# EmbeddedSystem_BackplaneV1.net
KiCad netlist of a schematic drawn in EAGLE
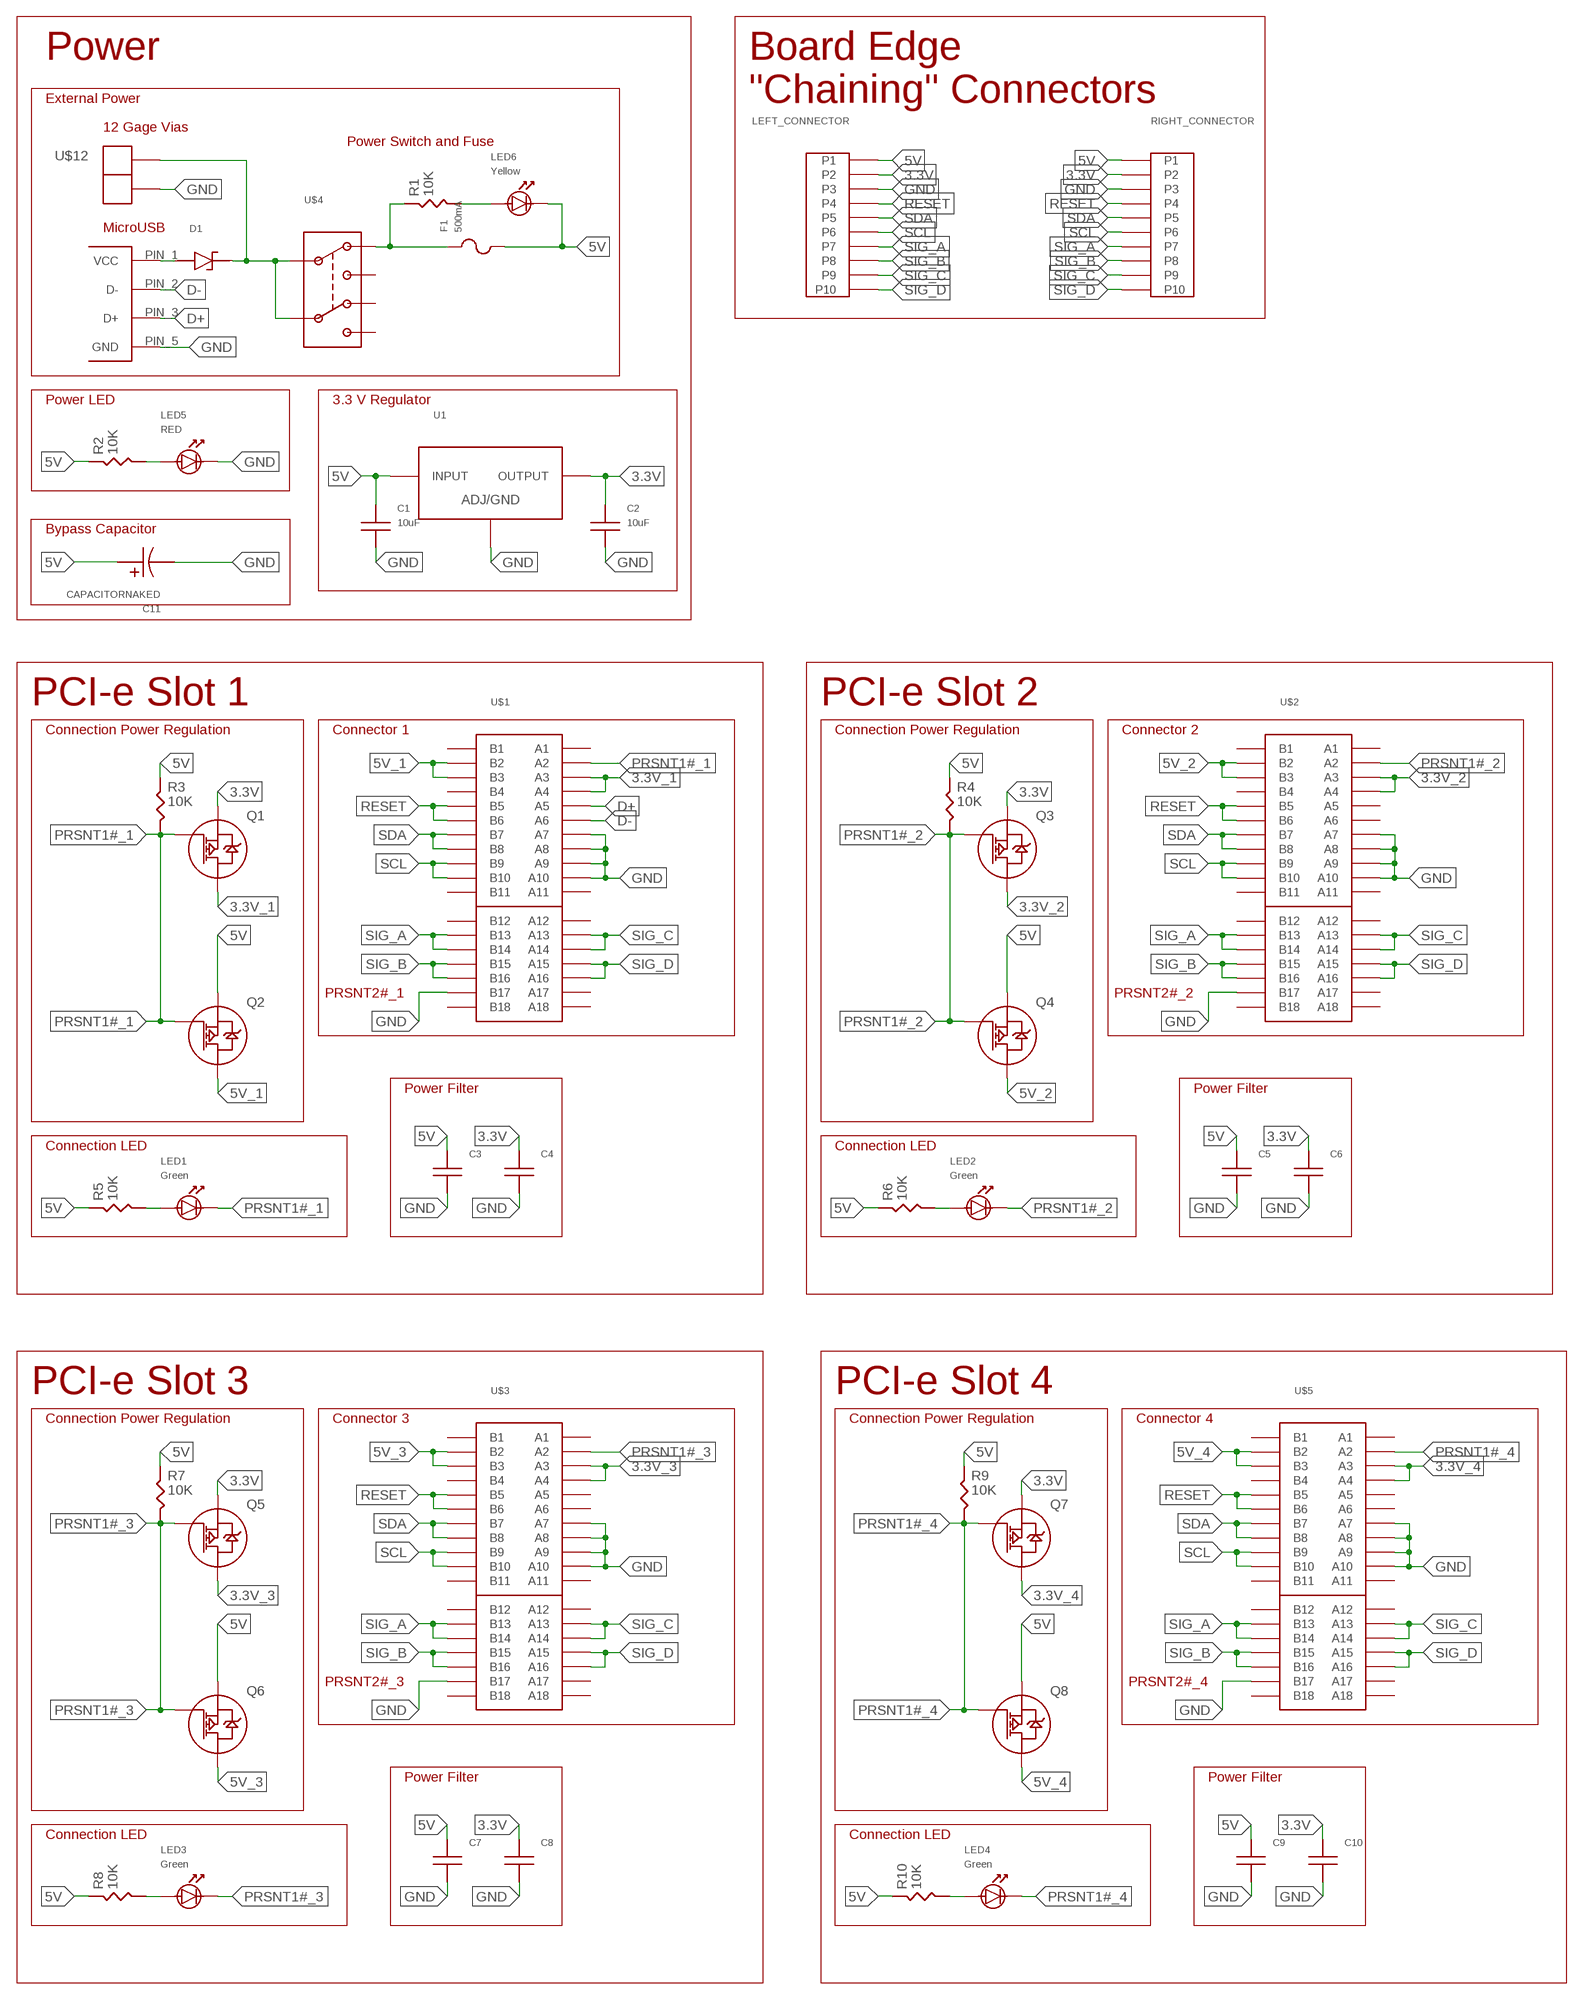
[diagram p0: schematic, sheet 1]

(export (version "E")
  (design (tool "Eeschema 10.0.6"))
  (components
    (comp (ref "C1")
      (value "10uF")
      (footprint "eagle-import:0805_STACKPOLERESISTOR")
      (libsource (lib "eagle-import") (part "CAPACITOR-UNPOLARIZED0805"))
    )
    (comp (ref "C2")
      (value "10uF")
      (footprint "eagle-import:0805_STACKPOLERESISTOR")
      (libsource (lib "eagle-import") (part "CAPACITOR-UNPOLARIZED0805"))
    )
    (comp (ref "C3")
      (value "CAPACITOR-UNPOLARIZED0805")
      (footprint "eagle-import:0805_STACKPOLERESISTOR")
      (libsource (lib "eagle-import") (part "CAPACITOR-UNPOLARIZED0805"))
    )
    (comp (ref "C4")
      (value "CAPACITOR-UNPOLARIZED0805")
      (footprint "eagle-import:0805_STACKPOLERESISTOR")
      (libsource (lib "eagle-import") (part "CAPACITOR-UNPOLARIZED0805"))
    )
    (comp (ref "C5")
      (value "CAPACITOR-UNPOLARIZED0805")
      (footprint "eagle-import:0805_STACKPOLERESISTOR")
      (libsource (lib "eagle-import") (part "CAPACITOR-UNPOLARIZED0805"))
    )
    (comp (ref "C6")
      (value "CAPACITOR-UNPOLARIZED0805")
      (footprint "eagle-import:0805_STACKPOLERESISTOR")
      (libsource (lib "eagle-import") (part "CAPACITOR-UNPOLARIZED0805"))
    )
    (comp (ref "C7")
      (value "CAPACITOR-UNPOLARIZED0805")
      (footprint "eagle-import:0805_STACKPOLERESISTOR")
      (libsource (lib "eagle-import") (part "CAPACITOR-UNPOLARIZED0805"))
    )
    (comp (ref "C8")
      (value "CAPACITOR-UNPOLARIZED0805")
      (footprint "eagle-import:0805_STACKPOLERESISTOR")
      (libsource (lib "eagle-import") (part "CAPACITOR-UNPOLARIZED0805"))
    )
    (comp (ref "C9")
      (value "CAPACITOR-UNPOLARIZED0805")
      (footprint "eagle-import:0805_STACKPOLERESISTOR")
      (libsource (lib "eagle-import") (part "CAPACITOR-UNPOLARIZED0805"))
    )
    (comp (ref "C10")
      (value "CAPACITOR-UNPOLARIZED0805")
      (footprint "eagle-import:0805_STACKPOLERESISTOR")
      (libsource (lib "eagle-import") (part "CAPACITOR-UNPOLARIZED0805"))
    )
    (comp (ref "C11")
      (value "CAPACITORNAKED")
      (footprint "eagle-import:ESK_H4_CAPACITOR_NAKED")
      (libsource (lib "eagle-import") (part "CAPACITORNAKED"))
    )
    (comp (ref "D1")
      (value "DIODE_SCHOTTKYSOD-123")
      (footprint "eagle-import:SOD-123")
      (libsource (lib "eagle-import") (part "DIODE_SCHOTTKYSOD-123"))
    )
    (comp (ref "F1")
      (value "500mA")
      (footprint "eagle-import:TYPE_C1Q_FUSE")
      (libsource (lib "eagle-import") (part "FUSEC1Q_SMD"))
    )
    (comp (ref "LED1")
      (value "Green")
      (footprint "eagle-import:0805_LED")
      (libsource (lib "eagle-import") (part "LED"))
    )
    (comp (ref "LED2")
      (value "Green")
      (footprint "eagle-import:0805_LED")
      (libsource (lib "eagle-import") (part "LED"))
    )
    (comp (ref "LED3")
      (value "Green")
      (footprint "eagle-import:0805_LED")
      (libsource (lib "eagle-import") (part "LED"))
    )
    (comp (ref "LED4")
      (value "Green")
      (footprint "eagle-import:0805_LED")
      (libsource (lib "eagle-import") (part "LED"))
    )
    (comp (ref "LED5")
      (value "RED")
      (footprint "eagle-import:0805_LED")
      (libsource (lib "eagle-import") (part "LED"))
    )
    (comp (ref "LED6")
      (value "Yellow")
      (footprint "eagle-import:0805_LED")
      (libsource (lib "eagle-import") (part "LED"))
    )
    (comp (ref "LEFT_CONNECTOR")
      (value "10PIN-HEADER")
      (footprint "eagle-import:10PIN_HEADER")
      (libsource (lib "eagle-import") (part "10PIN-HEADER"))
    )
    (comp (ref "Q1")
      (value "PMOSSOT-23")
      (footprint "eagle-import:SOT-23")
      (libsource (lib "eagle-import") (part "PMOSSOT-23"))
    )
    (comp (ref "Q2")
      (value "PMOSSOT-23")
      (footprint "eagle-import:SOT-23")
      (libsource (lib "eagle-import") (part "PMOSSOT-23"))
    )
    (comp (ref "Q3")
      (value "PMOSSOT-23")
      (footprint "eagle-import:SOT-23")
      (libsource (lib "eagle-import") (part "PMOSSOT-23"))
    )
    (comp (ref "Q4")
      (value "PMOSSOT-23")
      (footprint "eagle-import:SOT-23")
      (libsource (lib "eagle-import") (part "PMOSSOT-23"))
    )
    (comp (ref "Q5")
      (value "PMOSSOT-23")
      (footprint "eagle-import:SOT-23")
      (libsource (lib "eagle-import") (part "PMOSSOT-23"))
    )
    (comp (ref "Q6")
      (value "PMOSSOT-23")
      (footprint "eagle-import:SOT-23")
      (libsource (lib "eagle-import") (part "PMOSSOT-23"))
    )
    (comp (ref "Q7")
      (value "PMOSSOT-23")
      (footprint "eagle-import:SOT-23")
      (libsource (lib "eagle-import") (part "PMOSSOT-23"))
    )
    (comp (ref "Q8")
      (value "PMOSSOT-23")
      (footprint "eagle-import:SOT-23")
      (libsource (lib "eagle-import") (part "PMOSSOT-23"))
    )
    (comp (ref "R1")
      (value "10K")
      (footprint "eagle-import:0805_STACKPOLERESISTOR")
      (libsource (lib "eagle-import") (part "RESISTOR"))
    )
    (comp (ref "R2")
      (value "10K")
      (footprint "eagle-import:0805_STACKPOLERESISTOR")
      (libsource (lib "eagle-import") (part "RESISTOR"))
    )
    (comp (ref "R3")
      (value "10K")
      (footprint "eagle-import:0805_STACKPOLERESISTOR")
      (libsource (lib "eagle-import") (part "RESISTOR"))
    )
    (comp (ref "R4")
      (value "10K")
      (footprint "eagle-import:0805_STACKPOLERESISTOR")
      (libsource (lib "eagle-import") (part "RESISTOR"))
    )
    (comp (ref "R5")
      (value "10K")
      (footprint "eagle-import:0805_STACKPOLERESISTOR")
      (libsource (lib "eagle-import") (part "RESISTOR"))
    )
    (comp (ref "R6")
      (value "10K")
      (footprint "eagle-import:0805_STACKPOLERESISTOR")
      (libsource (lib "eagle-import") (part "RESISTOR"))
    )
    (comp (ref "R7")
      (value "10K")
      (footprint "eagle-import:0805_STACKPOLERESISTOR")
      (libsource (lib "eagle-import") (part "RESISTOR"))
    )
    (comp (ref "R8")
      (value "10K")
      (footprint "eagle-import:0805_STACKPOLERESISTOR")
      (libsource (lib "eagle-import") (part "RESISTOR"))
    )
    (comp (ref "R9")
      (value "10K")
      (footprint "eagle-import:0805_STACKPOLERESISTOR")
      (libsource (lib "eagle-import") (part "RESISTOR"))
    )
    (comp (ref "R10")
      (value "10K")
      (footprint "eagle-import:0805_STACKPOLERESISTOR")
      (libsource (lib "eagle-import") (part "RESISTOR"))
    )
    (comp (ref "RIGHT_CONNECTOR")
      (value "10PIN-HEADER")
      (footprint "eagle-import:10PIN_HEADER")
      (libsource (lib "eagle-import") (part "10PIN-HEADER"))
    )
    (comp (ref "U$1")
      (value "PCI-E_X1")
      (footprint "eagle-import:PCIE_X1")
      (libsource (lib "eagle-import") (part "PCI-E_X1"))
    )
    (comp (ref "U$2")
      (value "PCI-E_X1")
      (footprint "eagle-import:PCIE_X1")
      (libsource (lib "eagle-import") (part "PCI-E_X1"))
    )
    (comp (ref "U$3")
      (value "PCI-E_X1")
      (footprint "eagle-import:PCIE_X1")
      (libsource (lib "eagle-import") (part "PCI-E_X1"))
    )
    (comp (ref "U$4")
      (value "SWITCH_DPDT")
      (footprint "eagle-import:SWITCH_GF-126")
      (libsource (lib "eagle-import") (part "SWITCH_DPDT"))
    )
    (comp (ref "U$5")
      (value "PCI-E_X1")
      (footprint "eagle-import:PCIE_X1")
      (libsource (lib "eagle-import") (part "PCI-E_X1"))
    )
    (comp (ref "U$10")
      (value "USBMICROB")
      (footprint "eagle-import:USBMICROB-PAC")
      (libsource (lib "eagle-import") (part "USBMICROB"))
    )
    (comp (ref "U$12")
      (value "2PIN-HEADER16GAGE")
      (footprint "eagle-import:2PIN_16GAGE")
      (libsource (lib "eagle-import") (part "2PIN-HEADER16GAGE"))
    )
    (comp (ref "U1")
      (value "VOLTAGE_REGULATOR")
      (footprint "eagle-import:SOT223")
      (libsource (lib "eagle-import") (part "VOLTAGE_REGULATOR"))
    )
  )
  (nets
    (net (code "1") (name "3.3V") (class "Default")
      (node (ref "C10") (pin "P$1") (pinfunction "P$1_P$1") (pintype "bidirectional"))
      (node (ref "C2") (pin "P$1") (pinfunction "P$1_P$1") (pintype "bidirectional"))
      (node (ref "C4") (pin "P$1") (pinfunction "P$1_P$1") (pintype "bidirectional"))
      (node (ref "C6") (pin "P$1") (pinfunction "P$1_P$1") (pintype "bidirectional"))
      (node (ref "C8") (pin "P$1") (pinfunction "P$1_P$1") (pintype "bidirectional"))
      (node (ref "LEFT_CONNECTOR") (pin "P2") (pinfunction "P2_P2") (pintype "bidirectional"))
      (node (ref "Q1") (pin "S") (pinfunction "S_S") (pintype "bidirectional"))
      (node (ref "Q3") (pin "S") (pinfunction "S_S") (pintype "bidirectional"))
      (node (ref "Q5") (pin "S") (pinfunction "S_S") (pintype "bidirectional"))
      (node (ref "Q7") (pin "S") (pinfunction "S_S") (pintype "bidirectional"))
      (node (ref "RIGHT_CONNECTOR") (pin "P2") (pinfunction "P2_P2") (pintype "bidirectional"))
      (node (ref "U1") (pin "P2") (pinfunction "OUTPUT_P2") (pintype "bidirectional"))
      (node (ref "U1") (pin "TOP") (pinfunction "OUTPUT_TOP") (pintype "bidirectional"))
    )
    (net (code "2") (name "3.3V_1") (class "Default")
      (node (ref "Q1") (pin "D") (pinfunction "D_D") (pintype "bidirectional"))
      (node (ref "U$1") (pin "A3") (pinfunction "A3_A3") (pintype "bidirectional"))
      (node (ref "U$1") (pin "A4") (pinfunction "A4_A4") (pintype "bidirectional"))
    )
    (net (code "3") (name "3.3V_2") (class "Default")
      (node (ref "Q3") (pin "D") (pinfunction "D_D") (pintype "bidirectional"))
      (node (ref "U$2") (pin "A3") (pinfunction "A3_A3") (pintype "bidirectional"))
      (node (ref "U$2") (pin "A4") (pinfunction "A4_A4") (pintype "bidirectional"))
    )
    (net (code "4") (name "3.3V_3") (class "Default")
      (node (ref "Q5") (pin "D") (pinfunction "D_D") (pintype "bidirectional"))
      (node (ref "U$3") (pin "A3") (pinfunction "A3_A3") (pintype "bidirectional"))
      (node (ref "U$3") (pin "A4") (pinfunction "A4_A4") (pintype "bidirectional"))
    )
    (net (code "5") (name "3.3V_4") (class "Default")
      (node (ref "Q7") (pin "D") (pinfunction "D_D") (pintype "bidirectional"))
      (node (ref "U$5") (pin "A3") (pinfunction "A3_A3") (pintype "bidirectional"))
      (node (ref "U$5") (pin "A4") (pinfunction "A4_A4") (pintype "bidirectional"))
    )
    (net (code "6") (name "5V") (class "Default")
      (node (ref "C1") (pin "P$1") (pinfunction "P$1_P$1") (pintype "bidirectional"))
      (node (ref "C11") (pin "POSITIVE_PAD") (pinfunction "POSITIVE_LEAD_POSITIVE_PAD") (pintype "bidirectional"))
      (node (ref "C3") (pin "P$1") (pinfunction "P$1_P$1") (pintype "bidirectional"))
      (node (ref "C5") (pin "P$1") (pinfunction "P$1_P$1") (pintype "bidirectional"))
      (node (ref "C7") (pin "P$1") (pinfunction "P$1_P$1") (pintype "bidirectional"))
      (node (ref "C9") (pin "P$1") (pinfunction "P$1_P$1") (pintype "bidirectional"))
      (node (ref "F1") (pin "P$2") (pinfunction "P$2_P$2") (pintype "bidirectional"))
      (node (ref "LED6") (pin "CATHODE") (pinfunction "CATHODE_CATHODE") (pintype "bidirectional"))
      (node (ref "LEFT_CONNECTOR") (pin "P1") (pinfunction "P1_P1") (pintype "bidirectional"))
      (node (ref "Q2") (pin "S") (pinfunction "S_S") (pintype "bidirectional"))
      (node (ref "Q4") (pin "S") (pinfunction "S_S") (pintype "bidirectional"))
      (node (ref "Q6") (pin "S") (pinfunction "S_S") (pintype "bidirectional"))
      (node (ref "Q8") (pin "S") (pinfunction "S_S") (pintype "bidirectional"))
      (node (ref "R10") (pin "P$1") (pinfunction "P$1_P$1") (pintype "bidirectional"))
      (node (ref "R2") (pin "P$1") (pinfunction "P$1_P$1") (pintype "bidirectional"))
      (node (ref "R3") (pin "P$1") (pinfunction "P$1_P$1") (pintype "bidirectional"))
      (node (ref "R4") (pin "P$1") (pinfunction "P$1_P$1") (pintype "bidirectional"))
      (node (ref "R5") (pin "P$1") (pinfunction "P$1_P$1") (pintype "bidirectional"))
      (node (ref "R6") (pin "P$1") (pinfunction "P$1_P$1") (pintype "bidirectional"))
      (node (ref "R7") (pin "P$1") (pinfunction "P$1_P$1") (pintype "bidirectional"))
      (node (ref "R8") (pin "P$1") (pinfunction "P$1_P$1") (pintype "bidirectional"))
      (node (ref "R9") (pin "P$1") (pinfunction "P$1_P$1") (pintype "bidirectional"))
      (node (ref "RIGHT_CONNECTOR") (pin "P1") (pinfunction "P1_P1") (pintype "bidirectional"))
      (node (ref "U1") (pin "P3") (pinfunction "INPUT_P3") (pintype "bidirectional"))
    )
    (net (code "7") (name "5V_1") (class "Default")
      (node (ref "Q2") (pin "D") (pinfunction "D_D") (pintype "bidirectional"))
      (node (ref "U$1") (pin "B2") (pinfunction "B2_B2") (pintype "bidirectional"))
      (node (ref "U$1") (pin "B3") (pinfunction "B3_B3") (pintype "bidirectional"))
    )
    (net (code "8") (name "5V_2") (class "Default")
      (node (ref "Q4") (pin "D") (pinfunction "D_D") (pintype "bidirectional"))
      (node (ref "U$2") (pin "B2") (pinfunction "B2_B2") (pintype "bidirectional"))
      (node (ref "U$2") (pin "B3") (pinfunction "B3_B3") (pintype "bidirectional"))
    )
    (net (code "9") (name "5V_3") (class "Default")
      (node (ref "Q6") (pin "D") (pinfunction "D_D") (pintype "bidirectional"))
      (node (ref "U$3") (pin "B2") (pinfunction "B2_B2") (pintype "bidirectional"))
      (node (ref "U$3") (pin "B3") (pinfunction "B3_B3") (pintype "bidirectional"))
    )
    (net (code "10") (name "5V_4") (class "Default")
      (node (ref "Q8") (pin "D") (pinfunction "D_D") (pintype "bidirectional"))
      (node (ref "U$5") (pin "B2") (pinfunction "B2_B2") (pintype "bidirectional"))
      (node (ref "U$5") (pin "B3") (pinfunction "B3_B3") (pintype "bidirectional"))
    )
    (net (code "11") (name "D+") (class "Default")
      (node (ref "U$1") (pin "A5") (pinfunction "A5_A5") (pintype "bidirectional"))
      (node (ref "U$10") (pin "PIN_3") (pinfunction "D+_PIN_3") (pintype "bidirectional"))
    )
    (net (code "12") (name "D-") (class "Default")
      (node (ref "U$1") (pin "A6") (pinfunction "A6_A6") (pintype "bidirectional"))
      (node (ref "U$10") (pin "PIN_2") (pinfunction "D-_PIN_2") (pintype "bidirectional"))
    )
    (net (code "13") (name "GND") (class "Default")
      (node (ref "C1") (pin "P$2") (pinfunction "P$2_P$2") (pintype "bidirectional"))
      (node (ref "C10") (pin "P$2") (pinfunction "P$2_P$2") (pintype "bidirectional"))
      (node (ref "C11") (pin "NEGATIVE_PAD") (pinfunction "NEGATIVE_LEAD_NEGATIVE_PAD") (pintype "bidirectional"))
      (node (ref "C2") (pin "P$2") (pinfunction "P$2_P$2") (pintype "bidirectional"))
      (node (ref "C3") (pin "P$2") (pinfunction "P$2_P$2") (pintype "bidirectional"))
      (node (ref "C4") (pin "P$2") (pinfunction "P$2_P$2") (pintype "bidirectional"))
      (node (ref "C5") (pin "P$2") (pinfunction "P$2_P$2") (pintype "bidirectional"))
      (node (ref "C6") (pin "P$2") (pinfunction "P$2_P$2") (pintype "bidirectional"))
      (node (ref "C7") (pin "P$2") (pinfunction "P$2_P$2") (pintype "bidirectional"))
      (node (ref "C8") (pin "P$2") (pinfunction "P$2_P$2") (pintype "bidirectional"))
      (node (ref "C9") (pin "P$2") (pinfunction "P$2_P$2") (pintype "bidirectional"))
      (node (ref "LED5") (pin "CATHODE") (pinfunction "CATHODE_CATHODE") (pintype "bidirectional"))
      (node (ref "LEFT_CONNECTOR") (pin "P3") (pinfunction "P3_P3") (pintype "bidirectional"))
      (node (ref "RIGHT_CONNECTOR") (pin "P3") (pinfunction "P3_P3") (pintype "bidirectional"))
      (node (ref "U$1") (pin "A10") (pinfunction "A10_A10") (pintype "bidirectional"))
      (node (ref "U$1") (pin "A7") (pinfunction "A7_A7") (pintype "bidirectional"))
      (node (ref "U$1") (pin "A8") (pinfunction "A8_A8") (pintype "bidirectional"))
      (node (ref "U$1") (pin "A9") (pinfunction "A9_A9") (pintype "bidirectional"))
      (node (ref "U$1") (pin "B17") (pinfunction "B17_B17") (pintype "bidirectional"))
      (node (ref "U$10") (pin "PIN_5") (pinfunction "GND_PIN_5") (pintype "bidirectional"))
      (node (ref "U$12") (pin "P2") (pinfunction "P$2_P2") (pintype "bidirectional"))
      (node (ref "U$2") (pin "A10") (pinfunction "A10_A10") (pintype "bidirectional"))
      (node (ref "U$2") (pin "A7") (pinfunction "A7_A7") (pintype "bidirectional"))
      (node (ref "U$2") (pin "A8") (pinfunction "A8_A8") (pintype "bidirectional"))
      (node (ref "U$2") (pin "A9") (pinfunction "A9_A9") (pintype "bidirectional"))
      (node (ref "U$2") (pin "B17") (pinfunction "B17_B17") (pintype "bidirectional"))
      (node (ref "U$3") (pin "A10") (pinfunction "A10_A10") (pintype "bidirectional"))
      (node (ref "U$3") (pin "A7") (pinfunction "A7_A7") (pintype "bidirectional"))
      (node (ref "U$3") (pin "A8") (pinfunction "A8_A8") (pintype "bidirectional"))
      (node (ref "U$3") (pin "A9") (pinfunction "A9_A9") (pintype "bidirectional"))
      (node (ref "U$3") (pin "B17") (pinfunction "B17_B17") (pintype "bidirectional"))
      (node (ref "U$5") (pin "A10") (pinfunction "A10_A10") (pintype "bidirectional"))
      (node (ref "U$5") (pin "A7") (pinfunction "A7_A7") (pintype "bidirectional"))
      (node (ref "U$5") (pin "A8") (pinfunction "A8_A8") (pintype "bidirectional"))
      (node (ref "U$5") (pin "A9") (pinfunction "A9_A9") (pintype "bidirectional"))
      (node (ref "U$5") (pin "B17") (pinfunction "B17_B17") (pintype "bidirectional"))
      (node (ref "U1") (pin "P1") (pinfunction "ADJ/GND_P1") (pintype "bidirectional"))
    )
    (net (code "14") (name "Net-(F1-PadP$1)") (class "Default")
      (node (ref "F1") (pin "P$1") (pinfunction "P$1_P$1") (pintype "bidirectional"))
      (node (ref "R1") (pin "P$1") (pinfunction "P$1_P$1") (pintype "bidirectional"))
      (node (ref "U$4") (pin "P1_1") (pinfunction "P1_1_P1_1") (pintype "bidirectional"))
    )
    (net (code "15") (name "Net-(LED1-PadANODE)") (class "Default")
      (node (ref "LED1") (pin "ANODE") (pinfunction "ANODE_ANODE") (pintype "bidirectional"))
      (node (ref "R5") (pin "P$2") (pinfunction "P$2_P$2") (pintype "bidirectional"))
    )
    (net (code "16") (name "Net-(LED2-PadANODE)") (class "Default")
      (node (ref "LED2") (pin "ANODE") (pinfunction "ANODE_ANODE") (pintype "bidirectional"))
      (node (ref "R6") (pin "P$2") (pinfunction "P$2_P$2") (pintype "bidirectional"))
    )
    (net (code "17") (name "Net-(LED3-PadANODE)") (class "Default")
      (node (ref "LED3") (pin "ANODE") (pinfunction "ANODE_ANODE") (pintype "bidirectional"))
      (node (ref "R8") (pin "P$2") (pinfunction "P$2_P$2") (pintype "bidirectional"))
    )
    (net (code "18") (name "Net-(LED4-PadANODE)") (class "Default")
      (node (ref "LED4") (pin "ANODE") (pinfunction "ANODE_ANODE") (pintype "bidirectional"))
      (node (ref "R10") (pin "P$2") (pinfunction "P$2_P$2") (pintype "bidirectional"))
    )
    (net (code "19") (name "Net-(LED5-PadANODE)") (class "Default")
      (node (ref "LED5") (pin "ANODE") (pinfunction "ANODE_ANODE") (pintype "bidirectional"))
      (node (ref "R2") (pin "P$2") (pinfunction "P$2_P$2") (pintype "bidirectional"))
    )
    (net (code "20") (name "Net-(LED6-PadANODE)") (class "Default")
      (node (ref "LED6") (pin "ANODE") (pinfunction "ANODE_ANODE") (pintype "bidirectional"))
      (node (ref "R1") (pin "P$2") (pinfunction "P$2_P$2") (pintype "bidirectional"))
    )
    (net (code "21") (name "Net-(U$10-VCC)") (class "Default")
      (node (ref "D1") (pin "ANODE") (pinfunction "ANODE_ANODE") (pintype "bidirectional"))
      (node (ref "U$10") (pin "PIN_1") (pinfunction "VCC_PIN_1") (pintype "bidirectional"))
    )
    (net (code "22") (name "Net-(U$12-P$1)") (class "Default")
      (node (ref "D1") (pin "CATHODE") (pinfunction "CATHODE_CATHODE") (pintype "bidirectional"))
      (node (ref "U$12") (pin "P1") (pinfunction "P$1_P1") (pintype "bidirectional"))
      (node (ref "U$4") (pin "P1_C") (pinfunction "P1_C_P1_C") (pintype "bidirectional"))
      (node (ref "U$4") (pin "P2_C") (pinfunction "P2_C_P2_C") (pintype "bidirectional"))
    )
    (net (code "23") (name "PRSNT1#_1") (class "Default")
      (node (ref "LED1") (pin "CATHODE") (pinfunction "CATHODE_CATHODE") (pintype "bidirectional"))
      (node (ref "Q1") (pin "G") (pinfunction "G(1)_G") (pintype "bidirectional"))
      (node (ref "Q2") (pin "G") (pinfunction "G(1)_G") (pintype "bidirectional"))
      (node (ref "R3") (pin "P$2") (pinfunction "P$2_P$2") (pintype "bidirectional"))
      (node (ref "U$1") (pin "A2") (pinfunction "A2_A2") (pintype "bidirectional"))
    )
    (net (code "24") (name "PRSNT1#_2") (class "Default")
      (node (ref "LED2") (pin "CATHODE") (pinfunction "CATHODE_CATHODE") (pintype "bidirectional"))
      (node (ref "Q3") (pin "G") (pinfunction "G(1)_G") (pintype "bidirectional"))
      (node (ref "Q4") (pin "G") (pinfunction "G(1)_G") (pintype "bidirectional"))
      (node (ref "R4") (pin "P$2") (pinfunction "P$2_P$2") (pintype "bidirectional"))
      (node (ref "U$2") (pin "A2") (pinfunction "A2_A2") (pintype "bidirectional"))
    )
    (net (code "25") (name "PRSNT1#_3") (class "Default")
      (node (ref "LED3") (pin "CATHODE") (pinfunction "CATHODE_CATHODE") (pintype "bidirectional"))
      (node (ref "Q5") (pin "G") (pinfunction "G(1)_G") (pintype "bidirectional"))
      (node (ref "Q6") (pin "G") (pinfunction "G(1)_G") (pintype "bidirectional"))
      (node (ref "R7") (pin "P$2") (pinfunction "P$2_P$2") (pintype "bidirectional"))
      (node (ref "U$3") (pin "A2") (pinfunction "A2_A2") (pintype "bidirectional"))
    )
    (net (code "26") (name "PRSNT1#_4") (class "Default")
      (node (ref "LED4") (pin "CATHODE") (pinfunction "CATHODE_CATHODE") (pintype "bidirectional"))
      (node (ref "Q7") (pin "G") (pinfunction "G(1)_G") (pintype "bidirectional"))
      (node (ref "Q8") (pin "G") (pinfunction "G(1)_G") (pintype "bidirectional"))
      (node (ref "R9") (pin "P$2") (pinfunction "P$2_P$2") (pintype "bidirectional"))
      (node (ref "U$5") (pin "A2") (pinfunction "A2_A2") (pintype "bidirectional"))
    )
    (net (code "27") (name "RESET") (class "Default")
      (node (ref "LEFT_CONNECTOR") (pin "P4") (pinfunction "P4_P4") (pintype "bidirectional"))
      (node (ref "RIGHT_CONNECTOR") (pin "P4") (pinfunction "P4_P4") (pintype "bidirectional"))
      (node (ref "U$1") (pin "B5") (pinfunction "B5_B5") (pintype "bidirectional"))
      (node (ref "U$1") (pin "B6") (pinfunction "B6_B6") (pintype "bidirectional"))
      (node (ref "U$2") (pin "B5") (pinfunction "B5_B5") (pintype "bidirectional"))
      (node (ref "U$2") (pin "B6") (pinfunction "B6_B6") (pintype "bidirectional"))
      (node (ref "U$3") (pin "B5") (pinfunction "B5_B5") (pintype "bidirectional"))
      (node (ref "U$3") (pin "B6") (pinfunction "B6_B6") (pintype "bidirectional"))
      (node (ref "U$5") (pin "B5") (pinfunction "B5_B5") (pintype "bidirectional"))
      (node (ref "U$5") (pin "B6") (pinfunction "B6_B6") (pintype "bidirectional"))
    )
    (net (code "28") (name "SCL") (class "Default")
      (node (ref "LEFT_CONNECTOR") (pin "P6") (pinfunction "P6_P6") (pintype "bidirectional"))
      (node (ref "RIGHT_CONNECTOR") (pin "P6") (pinfunction "P6_P6") (pintype "bidirectional"))
      (node (ref "U$1") (pin "B10") (pinfunction "B10_B10") (pintype "bidirectional"))
      (node (ref "U$1") (pin "B9") (pinfunction "B9_B9") (pintype "bidirectional"))
      (node (ref "U$2") (pin "B10") (pinfunction "B10_B10") (pintype "bidirectional"))
      (node (ref "U$2") (pin "B9") (pinfunction "B9_B9") (pintype "bidirectional"))
      (node (ref "U$3") (pin "B10") (pinfunction "B10_B10") (pintype "bidirectional"))
      (node (ref "U$3") (pin "B9") (pinfunction "B9_B9") (pintype "bidirectional"))
      (node (ref "U$5") (pin "B10") (pinfunction "B10_B10") (pintype "bidirectional"))
      (node (ref "U$5") (pin "B9") (pinfunction "B9_B9") (pintype "bidirectional"))
    )
    (net (code "29") (name "SDA") (class "Default")
      (node (ref "LEFT_CONNECTOR") (pin "P5") (pinfunction "P5_P5") (pintype "bidirectional"))
      (node (ref "RIGHT_CONNECTOR") (pin "P5") (pinfunction "P5_P5") (pintype "bidirectional"))
      (node (ref "U$1") (pin "B7") (pinfunction "B7_B7") (pintype "bidirectional"))
      (node (ref "U$1") (pin "B8") (pinfunction "B8_B8") (pintype "bidirectional"))
      (node (ref "U$2") (pin "B7") (pinfunction "B7_B7") (pintype "bidirectional"))
      (node (ref "U$2") (pin "B8") (pinfunction "B8_B8") (pintype "bidirectional"))
      (node (ref "U$3") (pin "B7") (pinfunction "B7_B7") (pintype "bidirectional"))
      (node (ref "U$3") (pin "B8") (pinfunction "B8_B8") (pintype "bidirectional"))
      (node (ref "U$5") (pin "B7") (pinfunction "B7_B7") (pintype "bidirectional"))
      (node (ref "U$5") (pin "B8") (pinfunction "B8_B8") (pintype "bidirectional"))
    )
    (net (code "30") (name "SIG_A") (class "Default")
      (node (ref "LEFT_CONNECTOR") (pin "P7") (pinfunction "P7_P7") (pintype "bidirectional"))
      (node (ref "RIGHT_CONNECTOR") (pin "P7") (pinfunction "P7_P7") (pintype "bidirectional"))
      (node (ref "U$1") (pin "B13") (pinfunction "B13_B13") (pintype "bidirectional"))
      (node (ref "U$1") (pin "B14") (pinfunction "B14_B14") (pintype "bidirectional"))
      (node (ref "U$2") (pin "B13") (pinfunction "B13_B13") (pintype "bidirectional"))
      (node (ref "U$2") (pin "B14") (pinfunction "B14_B14") (pintype "bidirectional"))
      (node (ref "U$3") (pin "B13") (pinfunction "B13_B13") (pintype "bidirectional"))
      (node (ref "U$3") (pin "B14") (pinfunction "B14_B14") (pintype "bidirectional"))
      (node (ref "U$5") (pin "B13") (pinfunction "B13_B13") (pintype "bidirectional"))
      (node (ref "U$5") (pin "B14") (pinfunction "B14_B14") (pintype "bidirectional"))
    )
    (net (code "31") (name "SIG_B") (class "Default")
      (node (ref "LEFT_CONNECTOR") (pin "P8") (pinfunction "P8_P8") (pintype "bidirectional"))
      (node (ref "RIGHT_CONNECTOR") (pin "P8") (pinfunction "P8_P8") (pintype "bidirectional"))
      (node (ref "U$1") (pin "B15") (pinfunction "B15_B15") (pintype "bidirectional"))
      (node (ref "U$1") (pin "B16") (pinfunction "B16_B16") (pintype "bidirectional"))
      (node (ref "U$2") (pin "B15") (pinfunction "B15_B15") (pintype "bidirectional"))
      (node (ref "U$2") (pin "B16") (pinfunction "B16_B16") (pintype "bidirectional"))
      (node (ref "U$3") (pin "B15") (pinfunction "B15_B15") (pintype "bidirectional"))
      (node (ref "U$3") (pin "B16") (pinfunction "B16_B16") (pintype "bidirectional"))
      (node (ref "U$5") (pin "B15") (pinfunction "B15_B15") (pintype "bidirectional"))
      (node (ref "U$5") (pin "B16") (pinfunction "B16_B16") (pintype "bidirectional"))
    )
    (net (code "32") (name "SIG_C") (class "Default")
      (node (ref "LEFT_CONNECTOR") (pin "P9") (pinfunction "P9_P9") (pintype "bidirectional"))
      (node (ref "RIGHT_CONNECTOR") (pin "P9") (pinfunction "P9_P9") (pintype "bidirectional"))
      (node (ref "U$1") (pin "A13") (pinfunction "A13_A13") (pintype "bidirectional"))
      (node (ref "U$1") (pin "A14") (pinfunction "A14_A14") (pintype "bidirectional"))
      (node (ref "U$2") (pin "A13") (pinfunction "A13_A13") (pintype "bidirectional"))
      (node (ref "U$2") (pin "A14") (pinfunction "A14_A14") (pintype "bidirectional"))
      (node (ref "U$3") (pin "A13") (pinfunction "A13_A13") (pintype "bidirectional"))
      (node (ref "U$3") (pin "A14") (pinfunction "A14_A14") (pintype "bidirectional"))
      (node (ref "U$5") (pin "A13") (pinfunction "A13_A13") (pintype "bidirectional"))
      (node (ref "U$5") (pin "A14") (pinfunction "A14_A14") (pintype "bidirectional"))
    )
    (net (code "33") (name "SIG_D") (class "Default")
      (node (ref "LEFT_CONNECTOR") (pin "P10") (pinfunction "P10_P10") (pintype "bidirectional"))
      (node (ref "RIGHT_CONNECTOR") (pin "P10") (pinfunction "P10_P10") (pintype "bidirectional"))
      (node (ref "U$1") (pin "A15") (pinfunction "A15_A15") (pintype "bidirectional"))
      (node (ref "U$1") (pin "A16") (pinfunction "A16_A16") (pintype "bidirectional"))
      (node (ref "U$2") (pin "A15") (pinfunction "A15_A15") (pintype "bidirectional"))
      (node (ref "U$2") (pin "A16") (pinfunction "A16_A16") (pintype "bidirectional"))
      (node (ref "U$3") (pin "A15") (pinfunction "A15_A15") (pintype "bidirectional"))
      (node (ref "U$3") (pin "A16") (pinfunction "A16_A16") (pintype "bidirectional"))
      (node (ref "U$5") (pin "A15") (pinfunction "A15_A15") (pintype "bidirectional"))
      (node (ref "U$5") (pin "A16") (pinfunction "A16_A16") (pintype "bidirectional"))
    )
    (net (code "34") (name "unconnected-(U$1-PadA1)") (class "Default")
      (node (ref "U$1") (pin "A1") (pinfunction "A1_A1") (pintype "bidirectional"))
    )
    (net (code "35") (name "unconnected-(U$1-PadA11)") (class "Default")
      (node (ref "U$1") (pin "A11") (pinfunction "A11_A11") (pintype "bidirectional"))
    )
    (net (code "36") (name "unconnected-(U$1-PadA12)") (class "Default")
      (node (ref "U$1") (pin "A12") (pinfunction "A12_A12") (pintype "bidirectional"))
    )
    (net (code "37") (name "unconnected-(U$1-PadA17)") (class "Default")
      (node (ref "U$1") (pin "A17") (pinfunction "A17_A17") (pintype "bidirectional"))
    )
    (net (code "38") (name "unconnected-(U$1-PadA18)") (class "Default")
      (node (ref "U$1") (pin "A18") (pinfunction "A18_A18") (pintype "bidirectional"))
    )
    (net (code "39") (name "unconnected-(U$1-PadB1)") (class "Default")
      (node (ref "U$1") (pin "B1") (pinfunction "B1_B1") (pintype "bidirectional"))
    )
    (net (code "40") (name "unconnected-(U$1-PadB4)") (class "Default")
      (node (ref "U$1") (pin "B4") (pinfunction "B4_B4") (pintype "bidirectional"))
    )
    (net (code "41") (name "unconnected-(U$1-PadB11)") (class "Default")
      (node (ref "U$1") (pin "B11") (pinfunction "B11_B11") (pintype "bidirectional"))
    )
    (net (code "42") (name "unconnected-(U$1-PadB12)") (class "Default")
      (node (ref "U$1") (pin "B12") (pinfunction "B12_B12") (pintype "bidirectional"))
    )
    (net (code "43") (name "unconnected-(U$1-PadB18)") (class "Default")
      (node (ref "U$1") (pin "B18") (pinfunction "B18_B18") (pintype "bidirectional"))
    )
    (net (code "44") (name "unconnected-(U$2-PadA1)") (class "Default")
      (node (ref "U$2") (pin "A1") (pinfunction "A1_A1") (pintype "bidirectional"))
    )
    (net (code "45") (name "unconnected-(U$2-PadA5)") (class "Default")
      (node (ref "U$2") (pin "A5") (pinfunction "A5_A5") (pintype "bidirectional"))
    )
    (net (code "46") (name "unconnected-(U$2-PadA6)") (class "Default")
      (node (ref "U$2") (pin "A6") (pinfunction "A6_A6") (pintype "bidirectional"))
    )
    (net (code "47") (name "unconnected-(U$2-PadA11)") (class "Default")
      (node (ref "U$2") (pin "A11") (pinfunction "A11_A11") (pintype "bidirectional"))
    )
    (net (code "48") (name "unconnected-(U$2-PadA12)") (class "Default")
      (node (ref "U$2") (pin "A12") (pinfunction "A12_A12") (pintype "bidirectional"))
    )
    (net (code "49") (name "unconnected-(U$2-PadA17)") (class "Default")
      (node (ref "U$2") (pin "A17") (pinfunction "A17_A17") (pintype "bidirectional"))
    )
    (net (code "50") (name "unconnected-(U$2-PadA18)") (class "Default")
      (node (ref "U$2") (pin "A18") (pinfunction "A18_A18") (pintype "bidirectional"))
    )
    (net (code "51") (name "unconnected-(U$2-PadB1)") (class "Default")
      (node (ref "U$2") (pin "B1") (pinfunction "B1_B1") (pintype "bidirectional"))
    )
    (net (code "52") (name "unconnected-(U$2-PadB4)") (class "Default")
      (node (ref "U$2") (pin "B4") (pinfunction "B4_B4") (pintype "bidirectional"))
    )
    (net (code "53") (name "unconnected-(U$2-PadB11)") (class "Default")
      (node (ref "U$2") (pin "B11") (pinfunction "B11_B11") (pintype "bidirectional"))
    )
    (net (code "54") (name "unconnected-(U$2-PadB12)") (class "Default")
      (node (ref "U$2") (pin "B12") (pinfunction "B12_B12") (pintype "bidirectional"))
    )
    (net (code "55") (name "unconnected-(U$2-PadB18)") (class "Default")
      (node (ref "U$2") (pin "B18") (pinfunction "B18_B18") (pintype "bidirectional"))
    )
    (net (code "56") (name "unconnected-(U$3-PadA1)") (class "Default")
      (node (ref "U$3") (pin "A1") (pinfunction "A1_A1") (pintype "bidirectional"))
    )
    (net (code "57") (name "unconnected-(U$3-PadA5)") (class "Default")
      (node (ref "U$3") (pin "A5") (pinfunction "A5_A5") (pintype "bidirectional"))
    )
    (net (code "58") (name "unconnected-(U$3-PadA6)") (class "Default")
      (node (ref "U$3") (pin "A6") (pinfunction "A6_A6") (pintype "bidirectional"))
    )
    (net (code "59") (name "unconnected-(U$3-PadA11)") (class "Default")
      (node (ref "U$3") (pin "A11") (pinfunction "A11_A11") (pintype "bidirectional"))
    )
    (net (code "60") (name "unconnected-(U$3-PadA12)") (class "Default")
      (node (ref "U$3") (pin "A12") (pinfunction "A12_A12") (pintype "bidirectional"))
    )
    (net (code "61") (name "unconnected-(U$3-PadA17)") (class "Default")
      (node (ref "U$3") (pin "A17") (pinfunction "A17_A17") (pintype "bidirectional"))
    )
    (net (code "62") (name "unconnected-(U$3-PadA18)") (class "Default")
      (node (ref "U$3") (pin "A18") (pinfunction "A18_A18") (pintype "bidirectional"))
    )
    (net (code "63") (name "unconnected-(U$3-PadB1)") (class "Default")
      (node (ref "U$3") (pin "B1") (pinfunction "B1_B1") (pintype "bidirectional"))
    )
    (net (code "64") (name "unconnected-(U$3-PadB4)") (class "Default")
      (node (ref "U$3") (pin "B4") (pinfunction "B4_B4") (pintype "bidirectional"))
    )
    (net (code "65") (name "unconnected-(U$3-PadB11)") (class "Default")
      (node (ref "U$3") (pin "B11") (pinfunction "B11_B11") (pintype "bidirectional"))
    )
    (net (code "66") (name "unconnected-(U$3-PadB12)") (class "Default")
      (node (ref "U$3") (pin "B12") (pinfunction "B12_B12") (pintype "bidirectional"))
    )
    (net (code "67") (name "unconnected-(U$3-PadB18)") (class "Default")
      (node (ref "U$3") (pin "B18") (pinfunction "B18_B18") (pintype "bidirectional"))
    )
    (net (code "68") (name "unconnected-(U$4-PadP1_2)") (class "Default")
      (node (ref "U$4") (pin "P1_2") (pinfunction "P1_2_P1_2") (pintype "bidirectional"))
    )
    (net (code "69") (name "unconnected-(U$4-PadP2_1)") (class "Default")
      (node (ref "U$4") (pin "P2_1") (pinfunction "P2_1_P2_1") (pintype "bidirectional"))
    )
    (net (code "70") (name "unconnected-(U$4-PadP2_2)") (class "Default")
      (node (ref "U$4") (pin "P2_2") (pinfunction "P2_2_P2_2") (pintype "bidirectional"))
    )
    (net (code "71") (name "unconnected-(U$5-PadA1)") (class "Default")
      (node (ref "U$5") (pin "A1") (pinfunction "A1_A1") (pintype "bidirectional"))
    )
    (net (code "72") (name "unconnected-(U$5-PadA5)") (class "Default")
      (node (ref "U$5") (pin "A5") (pinfunction "A5_A5") (pintype "bidirectional"))
    )
    (net (code "73") (name "unconnected-(U$5-PadA6)") (class "Default")
      (node (ref "U$5") (pin "A6") (pinfunction "A6_A6") (pintype "bidirectional"))
    )
    (net (code "74") (name "unconnected-(U$5-PadA11)") (class "Default")
      (node (ref "U$5") (pin "A11") (pinfunction "A11_A11") (pintype "bidirectional"))
    )
    (net (code "75") (name "unconnected-(U$5-PadA12)") (class "Default")
      (node (ref "U$5") (pin "A12") (pinfunction "A12_A12") (pintype "bidirectional"))
    )
    (net (code "76") (name "unconnected-(U$5-PadA17)") (class "Default")
      (node (ref "U$5") (pin "A17") (pinfunction "A17_A17") (pintype "bidirectional"))
    )
    (net (code "77") (name "unconnected-(U$5-PadA18)") (class "Default")
      (node (ref "U$5") (pin "A18") (pinfunction "A18_A18") (pintype "bidirectional"))
    )
    (net (code "78") (name "unconnected-(U$5-PadB1)") (class "Default")
      (node (ref "U$5") (pin "B1") (pinfunction "B1_B1") (pintype "bidirectional"))
    )
    (net (code "79") (name "unconnected-(U$5-PadB4)") (class "Default")
      (node (ref "U$5") (pin "B4") (pinfunction "B4_B4") (pintype "bidirectional"))
    )
    (net (code "80") (name "unconnected-(U$5-PadB11)") (class "Default")
      (node (ref "U$5") (pin "B11") (pinfunction "B11_B11") (pintype "bidirectional"))
    )
    (net (code "81") (name "unconnected-(U$5-PadB12)") (class "Default")
      (node (ref "U$5") (pin "B12") (pinfunction "B12_B12") (pintype "bidirectional"))
    )
    (net (code "82") (name "unconnected-(U$5-PadB18)") (class "Default")
      (node (ref "U$5") (pin "B18") (pinfunction "B18_B18") (pintype "bidirectional"))
    )
  )
)
